# powersupply_grid8_1.net
KiCad netlist of a schematic drawn in Altium Designer
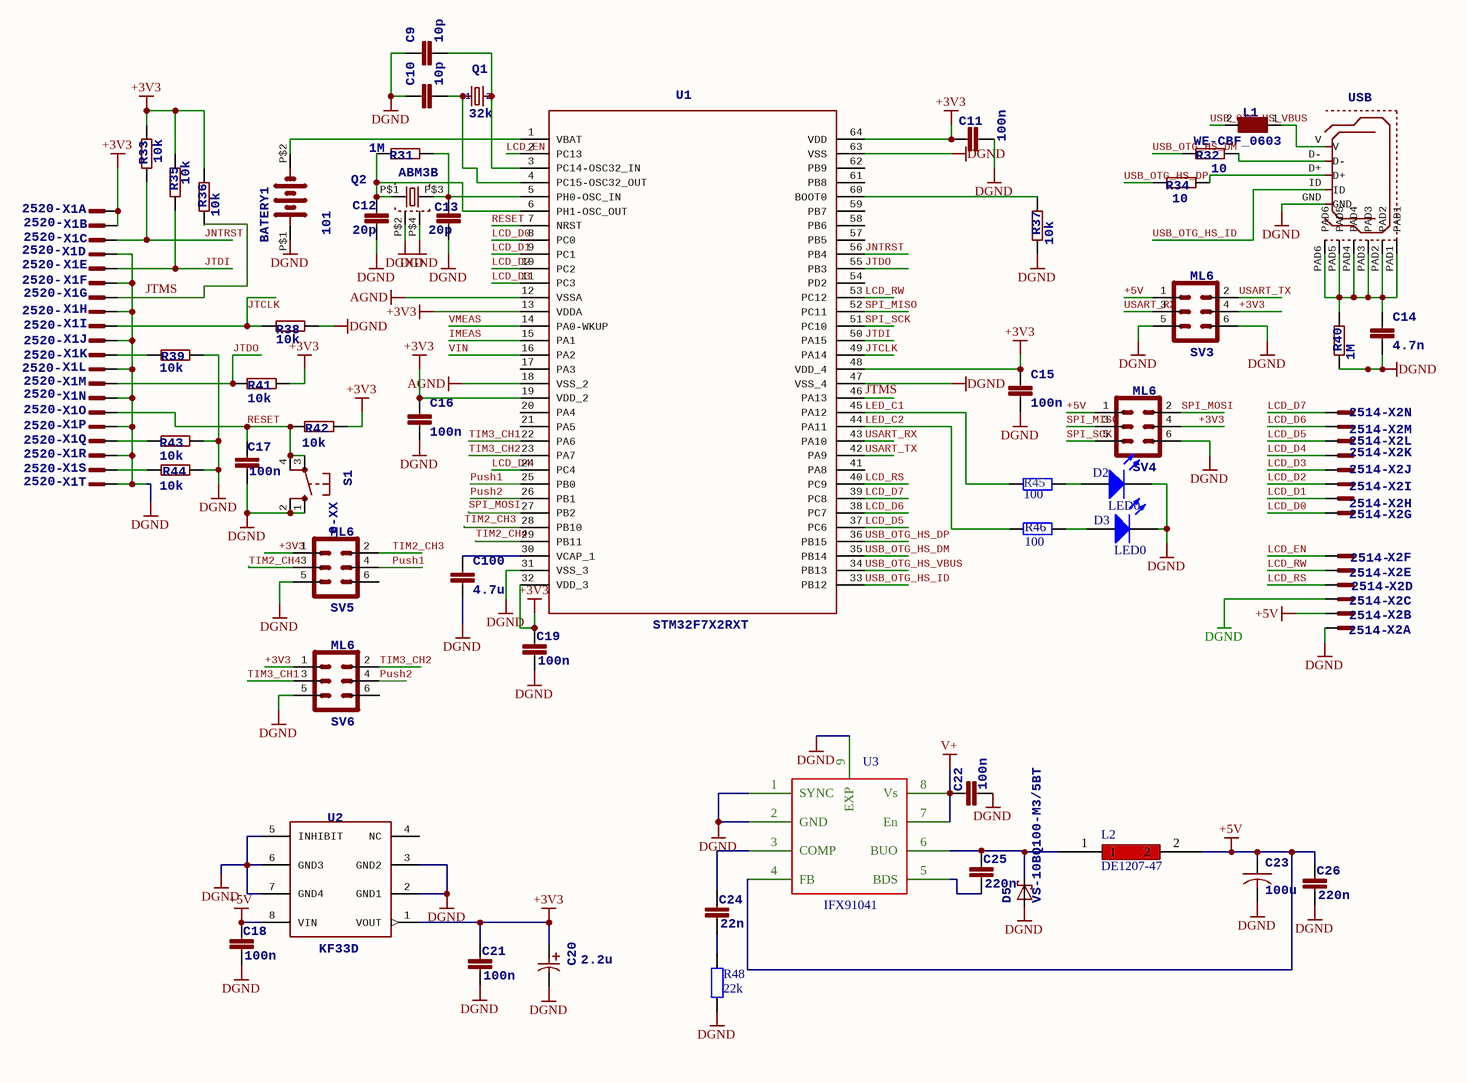
[diagram p0: powersupply_grid8_1.SchDoc]

(export (version "E")
  (design (tool "Eeschema 10.0.6"))
  (components
    (comp (ref "BATERY1") (value "101") (footprint "KEYSTONE101") (libsource (lib "my_battery") (part "101")))
    (comp (ref "C9")
      (value "10p")
      (footprint "C0402")
      (description "<B>CAPACITOR</B>, European symbol")
      (libsource (lib "") (part "C-EUC0402_1"))
    )
    (comp (ref "C10")
      (value "10p")
      (footprint "C0402")
      (description "<B>CAPACITOR</B>, European symbol")
      (libsource (lib "") (part "C-EUC0402_1"))
    )
    (comp (ref "C11")
      (value "100n")
      (footprint "C0402")
      (description "<B>CAPACITOR</B>, European symbol")
      (libsource (lib "") (part "C-EUC0402_1"))
    )
    (comp (ref "C12")
      (value "20p")
      (footprint "C0402")
      (description "<B>CAPACITOR</B>, European symbol")
      (libsource (lib "rcl") (part "C-EUC0402"))
    )
    (comp (ref "C13")
      (value "20p")
      (footprint "C0402")
      (description "<B>CAPACITOR</B>, European symbol")
      (libsource (lib "rcl") (part "C-EUC0402"))
    )
    (comp (ref "C14")
      (value "4.7n")
      (footprint "C0805")
      (description "<B>CAPACITOR</B>, European symbol")
      (libsource (lib "rcl") (part "C-EUC0805"))
    )
    (comp (ref "C15")
      (value "100n")
      (footprint "C0402")
      (description "<B>CAPACITOR</B>, European symbol")
      (libsource (lib "rcl") (part "C-EUC0402"))
    )
    (comp (ref "C16")
      (value "100n")
      (footprint "C0402")
      (description "<B>CAPACITOR</B>, European symbol")
      (libsource (lib "rcl") (part "C-EUC0402"))
    )
    (comp (ref "C17")
      (value "100n")
      (footprint "C0402")
      (description "<B>CAPACITOR</B>, European symbol")
      (libsource (lib "rcl") (part "C-EUC0402"))
    )
    (comp (ref "C18")
      (value "100n")
      (footprint "C0603")
      (description "<B>CAPACITOR</B>, European symbol")
      (libsource (lib "rcl") (part "C-EUC0603"))
    )
    (comp (ref "C19")
      (value "100n")
      (footprint "C0603")
      (description "<B>CAPACITOR</B>, European symbol")
      (libsource (lib "rcl") (part "C-EUC0603"))
    )
    (comp (ref "C20")
      (value "2.2u")
      (footprint "CAPAE430X610N")
      (fields
        (field (name "MPN") "EEE-FT0J101AR")
        (field (name "TOLERANCE") "±20 %")
        (field (name "MPN_1") "EEE-FT1A680AR")
      )
      (libsource (lib "Panasonic-EEEFT_EEEH") (part "EEE--CASE-B"))
    )
    (comp (ref "C21")
      (value "100n")
      (footprint "C0603")
      (description "<B>CAPACITOR</B>, European symbol")
      (libsource (lib "rcl") (part "C-EUC0603"))
    )
    (comp (ref "C22")
      (value "100n")
      (footprint "C0603")
      (description "<B>CAPACITOR</B>, European symbol")
      (libsource (lib "") (part "C-EUC0603_1"))
    )
    (comp (ref "C23") (value "100u") (footprint "C2225K") (libsource (lib "rcl") (part "C-USC2225K")))
    (comp (ref "C24")
      (value "22n")
      (footprint "C0603")
      (description "<B>CAPACITOR</B>, European symbol")
      (libsource (lib "rcl") (part "C-EUC0603"))
    )
    (comp (ref "C25")
      (value "220n")
      (footprint "C0603")
      (description "<B>CAPACITOR</B>, European symbol")
      (libsource (lib "rcl") (part "C-EUC0603"))
    )
    (comp (ref "C26")
      (value "220n")
      (footprint "C0603")
      (description "<B>CAPACITOR</B>, European symbol")
      (libsource (lib "rcl") (part "C-EUC0603"))
    )
    (comp (ref "C100") (value "4.7u") (footprint "C0805") (libsource (lib "rcl") (part "C-EUC0805")))
    (comp (ref "D2")
      (value "LED0")
      (footprint "LED-0")
      (description "Typical INFRARED GaAs LED")
      (fields (field (name "PUBLISHER") "Altium Limited"))
      (libsource (lib "Miscellaneous Devices") (part "LED0"))
    )
    (comp (ref "D3")
      (value "LED0")
      (footprint "LED-0")
      (description "Typical INFRARED GaAs LED")
      (fields (field (name "PUBLISHER") "Altium Limited"))
      (libsource (lib "Miscellaneous Devices") (part "LED0"))
    )
    (comp (ref "D5")
      (value "VS-10BQ100-M3/5BT")
      (footprint "DO214AA")
      (libsource (lib "VS-10BQ100-M3") (part "SCHOTTKY-DIODEAG"))
    )
    (comp (ref "L1")
      (value "WE-CBF_0603")
      (footprint "0603")
      (fields (field (name "MPN") "742792695"))
      (libsource (lib "WE-CBF") (part "WE-CBF_0603"))
    )
    (comp (ref "L2") (value "DE1207-47") (footprint "DE1207") (libsource (lib "de1207") (part "DE 1207")))
    (comp (ref "Q1")
      (value "32k")
      (footprint "TC26V")
      (description "<b>CRYSTAL</b>")
      (fields (field (name "1") "1") (field (name "2") "2"))
      (libsource (lib "crystal") (part "CRYSTALTC26V"))
    )
    (comp (ref "Q2") (value "ABM3B") (footprint "ABM3B") (libsource (lib "crystal_my") (part "ABM3B")))
    (comp (ref "R31")
      (value "1M")
      (footprint "R0402")
      (description "<B>RESISTOR</B>, European symbol")
      (libsource (lib "rcl") (part "R-EU_R0402"))
    )
    (comp (ref "R32")
      (value "10")
      (footprint "R0805")
      (description "<B>RESISTOR</B>, European symbol")
      (libsource (lib "rcl") (part "R-EU_R0805"))
    )
    (comp (ref "R33")
      (value "10k")
      (footprint "R0805")
      (description "<B>RESISTOR</B>, European symbol")
      (libsource (lib "rcl") (part "R-EU_R0805"))
    )
    (comp (ref "R34")
      (value "10")
      (footprint "R0805")
      (description "<B>RESISTOR</B>, European symbol")
      (libsource (lib "rcl") (part "R-EU_R0805"))
    )
    (comp (ref "R35")
      (value "10k")
      (footprint "R0805")
      (description "<B>RESISTOR</B>, European symbol")
      (libsource (lib "rcl") (part "R-EU_R0805"))
    )
    (comp (ref "R36")
      (value "10k")
      (footprint "R0805")
      (description "<B>RESISTOR</B>, European symbol")
      (libsource (lib "rcl") (part "R-EU_R0805"))
    )
    (comp (ref "R37")
      (value "10k")
      (footprint "R0805")
      (description "<B>RESISTOR</B>, European symbol")
      (libsource (lib "rcl") (part "R-EU_R0805"))
    )
    (comp (ref "R38")
      (value "10k")
      (footprint "R0805")
      (description "<B>RESISTOR</B>, European symbol")
      (libsource (lib "rcl") (part "R-EU_R0805"))
    )
    (comp (ref "R39")
      (value "10k")
      (footprint "R0805")
      (description "<B>RESISTOR</B>, European symbol")
      (libsource (lib "rcl") (part "R-EU_R0805"))
    )
    (comp (ref "R40")
      (value "1M")
      (footprint "R0805")
      (description "<B>RESISTOR</B>, European symbol")
      (libsource (lib "rcl") (part "R-EU_R0805"))
    )
    (comp (ref "R41")
      (value "10k")
      (footprint "R0805")
      (description "<B>RESISTOR</B>, European symbol")
      (libsource (lib "rcl") (part "R-EU_R0805"))
    )
    (comp (ref "R42")
      (value "10k")
      (footprint "R0805")
      (description "<B>RESISTOR</B>, European symbol")
      (libsource (lib "rcl") (part "R-EU_R0805"))
    )
    (comp (ref "R43")
      (value "10k")
      (footprint "R0805")
      (description "<B>RESISTOR</B>, European symbol")
      (libsource (lib "rcl") (part "R-EU_R0805"))
    )
    (comp (ref "R44")
      (value "10k")
      (footprint "R0805")
      (description "<B>RESISTOR</B>, European symbol")
      (libsource (lib "rcl") (part "R-EU_R0805"))
    )
    (comp (ref "R45")
      (value "100")
      (footprint "6-0805_L")
      (description "Resistor")
      (fields (field (name "Comment") "Res2") (field (name "PUBLISHER") "Altium Limited"))
      (libsource (lib "") (part "Res2_1"))
    )
    (comp (ref "R46")
      (value "100")
      (footprint "6-0805_L")
      (description "Resistor")
      (fields (field (name "Comment") "Res2") (field (name "PUBLISHER") "Altium Limited"))
      (libsource (lib "") (part "Res2_1"))
    )
    (comp (ref "R48")
      (value "22k")
      (footprint "6-0805_L")
      (description "Resistor")
      (fields (field (name "Comment") "Res2") (field (name "PUBLISHER") "Altium Limited"))
      (libsource (lib "Miscellaneous Devices") (part "Res2"))
    )
    (comp (ref "S1")
      (value "10-XX")
      (footprint "B3F-10XX")
      (description "<b>OMRON SWITCH</b>")
      (fields (field (name "MPN") "B3F-1000"))
      (libsource (lib "switch-omron") (part "10-XX"))
    )
    (comp (ref "SV3")
      (value "ML6")
      (footprint "ML6")
      (description "<b>HARTING</b>")
      (libsource (lib "con-harting-ml") (part "ML6"))
    )
    (comp (ref "SV4")
      (value "ML6")
      (footprint "ML6")
      (description "<b>HARTING</b>")
      (libsource (lib "con-harting-ml") (part "ML6"))
    )
    (comp (ref "SV5")
      (value "ML6")
      (footprint "ML6")
      (description "<b>HARTING</b>")
      (libsource (lib "con-harting-ml") (part "ML6"))
    )
    (comp (ref "SV6")
      (value "ML6")
      (footprint "ML6")
      (description "<b>HARTING</b>")
      (libsource (lib "con-harting-ml") (part "ML6"))
    )
    (comp (ref "U$4")
      (value "USB_MICROB")
      (footprint "USB_MICROB_PACKAGE")
      (description "This is the hirose ZX62-B-5PA(11) MICRO-USB B Type female connection.")
      (fields (field (name "USB") "USB"))
      (libsource (lib "usb_hinrose") (part "USB_MICROB"))
    )
    (comp (ref "U1")
      (value "STM32F7X2RXT")
      (footprint "LQFP64-10X10MM")
      (fields (field (name "MANUFACTURER_PART_NUMBER") "stm32f7x2rxt"))
      (libsource (lib "STM32F732RE") (part "STM32F7X2RXT"))
    )
    (comp (ref "U2") (value "KF33D") (footprint "SO8") (libsource (lib "KF33BD") (part "KF33D")))
    (comp (ref "U3")
      (value "IFX91041")
      (footprint "PG-DSO-8-27")
      (description "1.8A DC/DC Step-Down Voltage Regulator")
      (libsource (lib "IFX91041") (part "IFX91041"))
    )
    (comp (ref "X1")
      (value "2520-")
      (footprint "PAK100/2500-20")
      (description "<b>3M (TM) Pak 100 4-Wall Header</b><p>\nSource: 3M")
      (libsource (lib "con-3m") (part "2520-"))
    )
    (comp (ref "X2")
      (value "2514-")
      (footprint "PAK100/2500-14")
      (description "<b>3M (TM) Pak 100 4-Wall Header</b><p>\nSource: 3M")
      (libsource (lib "con-3m") (part "2514-"))
    )
  )
  (nets
    (net (code "1") (name "+3V3") (class "Default")
      (node (ref "C11") (pin "1") (pinfunction "1_1") (pintype "passive"))
      (node (ref "C15") (pin "1") (pinfunction "1_1") (pintype "passive"))
      (node (ref "C16") (pin "1") (pinfunction "1_1") (pintype "passive"))
      (node (ref "C19") (pin "1") (pinfunction "1_1") (pintype "passive"))
      (node (ref "C20") (pin "1") (pinfunction "1_1") (pintype "passive"))
      (node (ref "C21") (pin "1") (pinfunction "1_1") (pintype "passive"))
      (node (ref "R33") (pin "2") (pinfunction "2_2") (pintype "passive"))
      (node (ref "R35") (pin "2") (pinfunction "2_2") (pintype "passive"))
      (node (ref "R36") (pin "2") (pinfunction "2_2") (pintype "passive"))
      (node (ref "R41") (pin "1") (pinfunction "1_1") (pintype "passive"))
      (node (ref "R42") (pin "1") (pinfunction "1_1") (pintype "passive"))
      (node (ref "SV3") (pin "4") (pinfunction "4_4") (pintype "passive"))
      (node (ref "SV4") (pin "4") (pinfunction "4_4") (pintype "passive"))
      (node (ref "SV5") (pin "1") (pinfunction "1_1") (pintype "passive"))
      (node (ref "SV6") (pin "1") (pinfunction "1_1") (pintype "passive"))
      (node (ref "U1") (pin "13") (pinfunction "VDDA_13") (pintype "power_in"))
      (node (ref "U1") (pin "19") (pinfunction "VDD_2_19") (pintype "power_in"))
      (node (ref "U1") (pin "32") (pinfunction "VDD_3_32") (pintype "power_in"))
      (node (ref "U1") (pin "48") (pinfunction "VDD_4_48") (pintype "power_in"))
      (node (ref "U1") (pin "64") (pinfunction "VDD_64") (pintype "power_in"))
      (node (ref "U2") (pin "1") (pinfunction "VOUT_1") (pintype "output"))
      (node (ref "X1") (pin "1") (pinfunction "KL_1") (pintype "passive"))
      (node (ref "X1") (pin "2") (pinfunction "KL_2") (pintype "passive"))
    )
    (net (code "2") (name "+5V") (class "Default")
      (node (ref "C18") (pin "1") (pinfunction "1_1") (pintype "passive"))
      (node (ref "C23") (pin "1") (pinfunction "1_1") (pintype "passive"))
      (node (ref "C26") (pin "1") (pinfunction "1_1") (pintype "passive"))
      (node (ref "L2") (pin "2") (pinfunction "2_2") (pintype "passive"))
      (node (ref "SV3") (pin "1") (pinfunction "1_1") (pintype "passive"))
      (node (ref "SV4") (pin "1") (pinfunction "1_1") (pintype "passive"))
      (node (ref "U2") (pin "8") (pinfunction "VIN_8") (pintype "passive"))
      (node (ref "U3") (pin "4") (pinfunction "FB_4") (pintype "passive"))
      (node (ref "X2") (pin "2") (pinfunction "KL_2") (pintype "passive"))
    )
    (net (code "3") (name "/IMEAS") (class "Default")
      (node (ref "U1") (pin "15") (pinfunction "PA1_15") (pintype "passive"))
    )
    (net (code "4") (name "/JNTRST") (class "Default")
      (node (ref "R33") (pin "1") (pinfunction "1_1") (pintype "passive"))
      (node (ref "U1") (pin "56") (pinfunction "PB4_56") (pintype "passive"))
      (node (ref "X1") (pin "3") (pinfunction "KL_3") (pintype "passive"))
    )
    (net (code "5") (name "/JTCLK") (class "Default")
      (node (ref "R38") (pin "2") (pinfunction "2_2") (pintype "passive"))
      (node (ref "U1") (pin "49") (pinfunction "PA14_49") (pintype "passive"))
      (node (ref "X1") (pin "9") (pinfunction "KL_9") (pintype "passive"))
    )
    (net (code "6") (name "/JTDI") (class "Default")
      (node (ref "R35") (pin "1") (pinfunction "1_1") (pintype "passive"))
      (node (ref "U1") (pin "50") (pinfunction "PA15_50") (pintype "passive"))
      (node (ref "X1") (pin "5") (pinfunction "KL_5") (pintype "passive"))
    )
    (net (code "7") (name "/JTDO") (class "Default")
      (node (ref "R41") (pin "2") (pinfunction "2_2") (pintype "passive"))
      (node (ref "U1") (pin "55") (pinfunction "PB3_55") (pintype "passive"))
      (node (ref "X1") (pin "13") (pinfunction "KL_13") (pintype "passive"))
    )
    (net (code "8") (name "/JTMS") (class "Default")
      (node (ref "R36") (pin "1") (pinfunction "1_1") (pintype "passive"))
      (node (ref "U1") (pin "46") (pinfunction "PA13_46") (pintype "passive"))
      (node (ref "X1") (pin "7") (pinfunction "KL_7") (pintype "passive"))
    )
    (net (code "9") (name "/LCD_D0") (class "Default")
      (node (ref "U1") (pin "8") (pinfunction "PC0_8") (pintype "passive"))
      (node (ref "X2") (pin "7") (pinfunction "KL_7") (pintype "passive"))
    )
    (net (code "10") (name "/LCD_D1") (class "Default")
      (node (ref "U1") (pin "9") (pinfunction "PC1_9") (pintype "passive"))
      (node (ref "X2") (pin "8") (pinfunction "KL_8") (pintype "passive"))
    )
    (net (code "11") (name "/LCD_D2") (class "Default")
      (node (ref "U1") (pin "10") (pinfunction "PC2_10") (pintype "passive"))
      (node (ref "X2") (pin "9") (pinfunction "KL_9") (pintype "passive"))
    )
    (net (code "12") (name "/LCD_D3") (class "Default")
      (node (ref "U1") (pin "11") (pinfunction "PC3_11") (pintype "passive"))
      (node (ref "X2") (pin "10") (pinfunction "KL_10") (pintype "passive"))
    )
    (net (code "13") (name "/LCD_D4") (class "Default")
      (node (ref "U1") (pin "24") (pinfunction "PC4_24") (pintype "passive"))
      (node (ref "X2") (pin "11") (pinfunction "KL_11") (pintype "passive"))
    )
    (net (code "14") (name "/LCD_D5") (class "Default")
      (node (ref "U1") (pin "37") (pinfunction "PC6_37") (pintype "passive"))
      (node (ref "X2") (pin "12") (pinfunction "KL_12") (pintype "passive"))
    )
    (net (code "15") (name "/LCD_D6") (class "Default")
      (node (ref "U1") (pin "38") (pinfunction "PC7_38") (pintype "passive"))
      (node (ref "X2") (pin "13") (pinfunction "KL_13") (pintype "passive"))
    )
    (net (code "16") (name "/LCD_D7") (class "Default")
      (node (ref "U1") (pin "39") (pinfunction "PC8_39") (pintype "passive"))
      (node (ref "X2") (pin "14") (pinfunction "KL_14") (pintype "passive"))
    )
    (net (code "17") (name "/LCD_EN") (class "Default")
      (node (ref "U1") (pin "2") (pinfunction "PC13_2") (pintype "passive"))
      (node (ref "X2") (pin "6") (pinfunction "KL_6") (pintype "passive"))
    )
    (net (code "18") (name "/LCD_RS") (class "Default")
      (node (ref "U1") (pin "40") (pinfunction "PC9_40") (pintype "passive"))
      (node (ref "X2") (pin "4") (pinfunction "KL_4") (pintype "passive"))
    )
    (net (code "19") (name "/LCD_RW") (class "Default")
      (node (ref "U1") (pin "53") (pinfunction "PC12_53") (pintype "passive"))
      (node (ref "X2") (pin "5") (pinfunction "KL_5") (pintype "passive"))
    )
    (net (code "20") (name "/LED_C1") (class "Default")
      (node (ref "R45") (pin "1") (pinfunction "1_1") (pintype "passive"))
      (node (ref "U1") (pin "45") (pinfunction "PA12_45") (pintype "passive"))
    )
    (net (code "21") (name "/LED_C2") (class "Default")
      (node (ref "R46") (pin "1") (pinfunction "1_1") (pintype "passive"))
      (node (ref "U1") (pin "44") (pinfunction "PA11_44") (pintype "passive"))
    )
    (net (code "22") (name "/Push1") (class "Default")
      (node (ref "SV5") (pin "4") (pinfunction "4_4") (pintype "passive"))
      (node (ref "U1") (pin "25") (pinfunction "PB0_25") (pintype "passive"))
    )
    (net (code "23") (name "/Push2") (class "Default")
      (node (ref "SV6") (pin "4") (pinfunction "4_4") (pintype "passive"))
      (node (ref "U1") (pin "26") (pinfunction "PB1_26") (pintype "passive"))
    )
    (net (code "24") (name "/RESET") (class "Default")
      (node (ref "C17") (pin "1") (pinfunction "1_1") (pintype "passive"))
      (node (ref "R42") (pin "2") (pinfunction "2_2") (pintype "passive"))
      (node (ref "S1") (pin "3") (pinfunction "P_3") (pintype "passive"))
      (node (ref "S1") (pin "4") (pinfunction "P1_4") (pintype "passive"))
      (node (ref "U1") (pin "7") (pinfunction "NRST_7") (pintype "passive"))
      (node (ref "X1") (pin "15") (pinfunction "KL_15") (pintype "passive"))
    )
    (net (code "25") (name "/SPI_MISO") (class "Default")
      (node (ref "SV4") (pin "3") (pinfunction "3_3") (pintype "passive"))
      (node (ref "U1") (pin "52") (pinfunction "PC11_52") (pintype "passive"))
    )
    (net (code "26") (name "/SPI_MOSI") (class "Default")
      (node (ref "SV4") (pin "2") (pinfunction "2_2") (pintype "passive"))
      (node (ref "U1") (pin "27") (pinfunction "PB2_27") (pintype "passive"))
    )
    (net (code "27") (name "/SPI_SCK") (class "Default")
      (node (ref "SV4") (pin "5") (pinfunction "5_5") (pintype "passive"))
      (node (ref "U1") (pin "51") (pinfunction "PC10_51") (pintype "passive"))
    )
    (net (code "28") (name "/TIM2_CH3") (class "Default")
      (node (ref "SV5") (pin "2") (pinfunction "2_2") (pintype "passive"))
      (node (ref "U1") (pin "28") (pinfunction "PB10_28") (pintype "passive"))
    )
    (net (code "29") (name "/TIM2_CH4") (class "Default")
      (node (ref "SV5") (pin "3") (pinfunction "3_3") (pintype "passive"))
      (node (ref "U1") (pin "29") (pinfunction "PB11_29") (pintype "passive"))
    )
    (net (code "30") (name "/TIM3_CH1") (class "Default")
      (node (ref "SV6") (pin "3") (pinfunction "3_3") (pintype "passive"))
      (node (ref "U1") (pin "22") (pinfunction "PA6_22") (pintype "passive"))
    )
    (net (code "31") (name "/TIM3_CH2") (class "Default")
      (node (ref "SV6") (pin "2") (pinfunction "2_2") (pintype "passive"))
      (node (ref "U1") (pin "23") (pinfunction "PA7_23") (pintype "passive"))
    )
    (net (code "32") (name "/USART_RX") (class "Default")
      (node (ref "SV3") (pin "3") (pinfunction "3_3") (pintype "passive"))
      (node (ref "U1") (pin "43") (pinfunction "PA10_43") (pintype "passive"))
    )
    (net (code "33") (name "/USART_TX") (class "Default")
      (node (ref "SV3") (pin "2") (pinfunction "2_2") (pintype "passive"))
      (node (ref "U1") (pin "42") (pinfunction "PA9_42") (pintype "passive"))
    )
    (net (code "34") (name "/USB_OTG_HS_DM") (class "Default")
      (node (ref "R32") (pin "2") (pinfunction "2_2") (pintype "passive"))
      (node (ref "U1") (pin "35") (pinfunction "PB14_35") (pintype "passive"))
    )
    (net (code "35") (name "/USB_OTG_HS_DP") (class "Default")
      (node (ref "R34") (pin "2") (pinfunction "2_2") (pintype "passive"))
      (node (ref "U1") (pin "36") (pinfunction "PB15_36") (pintype "passive"))
    )
    (net (code "36") (name "/USB_OTG_HS_ID") (class "Default")
      (node (ref "U$4") (pin "ID") (pinfunction "ID_ID") (pintype "passive"))
      (node (ref "U1") (pin "33") (pinfunction "PB12_33") (pintype "passive"))
    )
    (net (code "37") (name "/USB_OTG_HS_VBUS") (class "Default")
      (node (ref "L1") (pin "2") (pinfunction "2_2") (pintype "passive"))
      (node (ref "U1") (pin "34") (pinfunction "PB13_34") (pintype "passive"))
    )
    (net (code "38") (name "/VIN") (class "Default")
      (node (ref "U1") (pin "16") (pinfunction "PA2_16") (pintype "passive"))
    )
    (net (code "39") (name "/VMEAS") (class "Default")
      (node (ref "U1") (pin "14") (pinfunction "PA0-WKUP_14") (pintype "passive"))
    )
    (net (code "40") (name "AGND") (class "Default")
      (node (ref "U1") (pin "12") (pinfunction "VSSA_12") (pintype "power_in"))
      (node (ref "U1") (pin "18") (pinfunction "VSS_2_18") (pintype "power_in"))
    )
    (net (code "41") (name "DGND") (class "Default")
      (node (ref "BATERY1") (pin "P$1") (pinfunction "+_P$1") (pintype "passive"))
      (node (ref "C10") (pin "1") (pinfunction "1_1") (pintype "passive"))
      (node (ref "C100") (pin "2") (pinfunction "2_2") (pintype "passive"))
      (node (ref "C11") (pin "2") (pinfunction "2_2") (pintype "passive"))
      (node (ref "C12") (pin "2") (pinfunction "2_2") (pintype "passive"))
      (node (ref "C13") (pin "2") (pinfunction "2_2") (pintype "passive"))
      (node (ref "C14") (pin "2") (pinfunction "2_2") (pintype "passive"))
      (node (ref "C15") (pin "2") (pinfunction "2_2") (pintype "passive"))
      (node (ref "C16") (pin "2") (pinfunction "2_2") (pintype "passive"))
      (node (ref "C17") (pin "2") (pinfunction "2_2") (pintype "passive"))
      (node (ref "C18") (pin "2") (pinfunction "2_2") (pintype "passive"))
      (node (ref "C19") (pin "2") (pinfunction "2_2") (pintype "passive"))
      (node (ref "C20") (pin "2") (pinfunction "2_2") (pintype "passive"))
      (node (ref "C21") (pin "2") (pinfunction "2_2") (pintype "passive"))
      (node (ref "C22") (pin "2") (pinfunction "2_2") (pintype "passive"))
      (node (ref "C23") (pin "2") (pinfunction "2_2") (pintype "passive"))
      (node (ref "C26") (pin "2") (pinfunction "2_2") (pintype "passive"))
      (node (ref "C9") (pin "1") (pinfunction "1_1") (pintype "passive"))
      (node (ref "D2") (pin "2") (pinfunction "K_2") (pintype "passive"))
      (node (ref "D3") (pin "2") (pinfunction "K_2") (pintype "passive"))
      (node (ref "D5") (pin "A") (pinfunction "A_A") (pintype "passive"))
      (node (ref "Q2") (pin "P$2") (pinfunction "2_P$2") (pintype "passive"))
      (node (ref "Q2") (pin "P$4") (pinfunction "4_P$4") (pintype "passive"))
      (node (ref "R37") (pin "1") (pinfunction "1_1") (pintype "passive"))
      (node (ref "R38") (pin "1") (pinfunction "1_1") (pintype "passive"))
      (node (ref "R39") (pin "1") (pinfunction "1_1") (pintype "passive"))
      (node (ref "R40") (pin "1") (pinfunction "1_1") (pintype "passive"))
      (node (ref "R43") (pin "1") (pinfunction "1_1") (pintype "passive"))
      (node (ref "R44") (pin "1") (pinfunction "1_1") (pintype "passive"))
      (node (ref "R48") (pin "1") (pinfunction "1_1") (pintype "passive"))
      (node (ref "S1") (pin "1") (pinfunction "S_1") (pintype "passive"))
      (node (ref "S1") (pin "2") (pinfunction "S1_2") (pintype "passive"))
      (node (ref "SV3") (pin "5") (pinfunction "5_5") (pintype "passive"))
      (node (ref "SV3") (pin "6") (pinfunction "6_6") (pintype "passive"))
      (node (ref "SV4") (pin "6") (pinfunction "6_6") (pintype "passive"))
      (node (ref "SV5") (pin "5") (pinfunction "5_5") (pintype "passive"))
      (node (ref "SV6") (pin "5") (pinfunction "5_5") (pintype "passive"))
      (node (ref "U$4") (pin "GND") (pinfunction "GND_GND") (pintype "passive"))
      (node (ref "U1") (pin "31") (pinfunction "VSS_3_31") (pintype "power_in"))
      (node (ref "U1") (pin "47") (pinfunction "VSS_4_47") (pintype "power_in"))
      (node (ref "U1") (pin "63") (pinfunction "VSS_63") (pintype "power_in"))
      (node (ref "U2") (pin "2") (pinfunction "GND1_2") (pintype "power_in"))
      (node (ref "U2") (pin "3") (pinfunction "GND2_3") (pintype "power_in"))
      (node (ref "U2") (pin "5") (pinfunction "INHIBIT_5") (pintype "passive"))
      (node (ref "U2") (pin "6") (pinfunction "GND3_6") (pintype "power_in"))
      (node (ref "U2") (pin "7") (pinfunction "GND4_7") (pintype "power_in"))
      (node (ref "U3") (pin "1") (pinfunction "SYNC_1") (pintype "passive"))
      (node (ref "U3") (pin "2") (pinfunction "GND_2") (pintype "passive"))
      (node (ref "U3") (pin "9") (pinfunction "EXP_9") (pintype "passive"))
      (node (ref "X1") (pin "10") (pinfunction "KL_10") (pintype "passive"))
      (node (ref "X1") (pin "12") (pinfunction "KL_12") (pintype "passive"))
      (node (ref "X1") (pin "14") (pinfunction "KL_14") (pintype "passive"))
      (node (ref "X1") (pin "16") (pinfunction "KL_16") (pintype "passive"))
      (node (ref "X1") (pin "18") (pinfunction "KL_18") (pintype "passive"))
      (node (ref "X1") (pin "20") (pinfunction "KL_20") (pintype "passive"))
      (node (ref "X1") (pin "4") (pinfunction "KL_4") (pintype "passive"))
      (node (ref "X1") (pin "6") (pinfunction "KL_6") (pintype "passive"))
      (node (ref "X1") (pin "8") (pinfunction "KL_8") (pintype "passive"))
      (node (ref "X2") (pin "1") (pinfunction "KL_1") (pintype "passive"))
      (node (ref "X2") (pin "3") (pinfunction "KL_3") (pintype "passive"))
    )
    (net (code "42") (name "Net-(BATERY1--)") (class "Default")
      (node (ref "BATERY1") (pin "P$2") (pinfunction "-_P$2") (pintype "passive"))
      (node (ref "U1") (pin "1") (pinfunction "VBAT_1") (pintype "power_in"))
    )
    (net (code "43") (name "Net-(C14-Pad1)") (class "Default")
      (node (ref "C14") (pin "1") (pinfunction "1_1") (pintype "passive"))
      (node (ref "R40") (pin "2") (pinfunction "2_2") (pintype "passive"))
      (node (ref "U$4") (pin "PAD1") (pinfunction "PAD1_PAD1") (pintype "passive"))
      (node (ref "U$4") (pin "PAD2") (pinfunction "PAD2_PAD2") (pintype "passive"))
      (node (ref "U$4") (pin "PAD3") (pinfunction "PAD3_PAD3") (pintype "passive"))
      (node (ref "U$4") (pin "PAD4") (pinfunction "PAD4_PAD4") (pintype "passive"))
      (node (ref "U$4") (pin "PAD5") (pinfunction "PAD5_PAD5") (pintype "passive"))
      (node (ref "U$4") (pin "PAD6") (pinfunction "PAD6_PAD6") (pintype "passive"))
    )
    (net (code "44") (name "Net-(C24-Pad2)") (class "Default")
      (node (ref "C24") (pin "2") (pinfunction "2_2") (pintype "passive"))
      (node (ref "R48") (pin "2") (pinfunction "2_2") (pintype "passive"))
    )
    (net (code "45") (name "Net-(D2-A)") (class "Default")
      (node (ref "D2") (pin "1") (pinfunction "A_1") (pintype "passive"))
      (node (ref "R45") (pin "2") (pinfunction "2_2") (pintype "passive"))
    )
    (net (code "46") (name "Net-(D3-A)") (class "Default")
      (node (ref "D3") (pin "1") (pinfunction "A_1") (pintype "passive"))
      (node (ref "R46") (pin "2") (pinfunction "2_2") (pintype "passive"))
    )
    (net (code "47") (name "Net-(L1-Pad1)") (class "Default")
      (node (ref "L1") (pin "1") (pinfunction "1_1") (pintype "passive"))
      (node (ref "U$4") (pin "V") (pinfunction "V_V") (pintype "passive"))
    )
    (net (code "48") (name "Net-(Q2-1)") (class "Default")
      (node (ref "C12") (pin "1") (pinfunction "1_1") (pintype "passive"))
      (node (ref "Q2") (pin "P$1") (pinfunction "1_P$1") (pintype "passive"))
      (node (ref "R31") (pin "2") (pinfunction "2_2") (pintype "passive"))
      (node (ref "U1") (pin "6") (pinfunction "PH1-OSC_OUT_6") (pintype "passive"))
    )
    (net (code "49") (name "Net-(Q2-3)") (class "Default")
      (node (ref "C13") (pin "1") (pinfunction "1_1") (pintype "passive"))
      (node (ref "Q2") (pin "P$3") (pinfunction "3_P$3") (pintype "passive"))
      (node (ref "R31") (pin "1") (pinfunction "1_1") (pintype "passive"))
      (node (ref "U1") (pin "5") (pinfunction "PH0-OSC_IN_5") (pintype "passive"))
    )
    (net (code "50") (name "Net-(R32-Pad1)") (class "Default")
      (node (ref "R32") (pin "1") (pinfunction "1_1") (pintype "passive"))
      (node (ref "U$4") (pin "D-") (pinfunction "D-_D-") (pintype "passive"))
    )
    (net (code "51") (name "Net-(R34-Pad1)") (class "Default")
      (node (ref "R34") (pin "1") (pinfunction "1_1") (pintype "passive"))
      (node (ref "U$4") (pin "D+") (pinfunction "D+_D+") (pintype "passive"))
    )
    (net (code "52") (name "Net-(U1-BOOT0)") (class "Default")
      (node (ref "R37") (pin "2") (pinfunction "2_2") (pintype "passive"))
      (node (ref "U1") (pin "60") (pinfunction "BOOT0_60") (pintype "passive"))
    )
    (net (code "53") (name "Net-(U1-PC14-OSC32_IN)") (class "Default")
      (node (ref "C9") (pin "2") (pinfunction "2_2") (pintype "passive"))
      (node (ref "Q1") (pin "2") (pinfunction "2_2") (pintype "passive"))
      (node (ref "U1") (pin "3") (pinfunction "PC14-OSC32_IN_3") (pintype "passive"))
    )
    (net (code "54") (name "Net-(U1-PC15-OSC32_OUT)") (class "Default")
      (node (ref "C10") (pin "2") (pinfunction "2_2") (pintype "passive"))
      (node (ref "Q1") (pin "1") (pinfunction "1_1") (pintype "passive"))
      (node (ref "U1") (pin "4") (pinfunction "PC15-OSC32_OUT_4") (pintype "passive"))
    )
    (net (code "55") (name "Net-(U1-VCAP_1)") (class "Default")
      (node (ref "C100") (pin "1") (pinfunction "1_1") (pintype "passive"))
      (node (ref "U1") (pin "30") (pinfunction "VCAP_1_30") (pintype "power_in"))
    )
    (net (code "56") (name "Net-(U3-BDS)") (class "Default")
      (node (ref "C25") (pin "2") (pinfunction "2_2") (pintype "passive"))
      (node (ref "U3") (pin "5") (pinfunction "BDS_5") (pintype "passive"))
    )
    (net (code "57") (name "Net-(U3-BUO)") (class "Default")
      (node (ref "C25") (pin "1") (pinfunction "1_1") (pintype "passive"))
      (node (ref "D5") (pin "C") (pinfunction "C_C") (pintype "passive"))
      (node (ref "L2") (pin "1") (pinfunction "1_1") (pintype "passive"))
      (node (ref "U3") (pin "6") (pinfunction "BUO_6") (pintype "passive"))
    )
    (net (code "58") (name "Net-(U3-COMP)") (class "Default")
      (node (ref "C24") (pin "1") (pinfunction "1_1") (pintype "passive"))
      (node (ref "U3") (pin "3") (pinfunction "COMP_3") (pintype "passive"))
    )
    (net (code "59") (name "Net-(X1K-KL)") (class "Default")
      (node (ref "R39") (pin "2") (pinfunction "2_2") (pintype "passive"))
      (node (ref "X1") (pin "11") (pinfunction "KL_11") (pintype "passive"))
    )
    (net (code "60") (name "Net-(X1Q-KL)") (class "Default")
      (node (ref "R43") (pin "2") (pinfunction "2_2") (pintype "passive"))
      (node (ref "X1") (pin "17") (pinfunction "KL_17") (pintype "passive"))
    )
    (net (code "61") (name "Net-(X1S-KL)") (class "Default")
      (node (ref "R44") (pin "2") (pinfunction "2_2") (pintype "passive"))
      (node (ref "X1") (pin "19") (pinfunction "KL_19") (pintype "passive"))
    )
    (net (code "62") (name "V+") (class "Default")
      (node (ref "C22") (pin "1") (pinfunction "1_1") (pintype "passive"))
      (node (ref "U3") (pin "7") (pinfunction "En_7") (pintype "passive"))
      (node (ref "U3") (pin "8") (pinfunction "Vs_8") (pintype "passive"))
    )
    (net (code "63") (name "unconnected-(SV5-Pad6)") (class "Default")
      (node (ref "SV5") (pin "6") (pinfunction "6_6") (pintype "passive"))
    )
    (net (code "64") (name "unconnected-(SV6-Pad6)") (class "Default")
      (node (ref "SV6") (pin "6") (pinfunction "6_6") (pintype "passive"))
    )
    (net (code "65") (name "unconnected-(U1-PA3-Pad17)") (class "Default")
      (node (ref "U1") (pin "17") (pinfunction "PA3_17") (pintype "passive"))
    )
    (net (code "66") (name "unconnected-(U1-PA4-Pad20)") (class "Default")
      (node (ref "U1") (pin "20") (pinfunction "PA4_20") (pintype "passive"))
    )
    (net (code "67") (name "unconnected-(U1-PA5-Pad21)") (class "Default")
      (node (ref "U1") (pin "21") (pinfunction "PA5_21") (pintype "passive"))
    )
    (net (code "68") (name "unconnected-(U1-PA8-Pad41)") (class "Default")
      (node (ref "U1") (pin "41") (pinfunction "PA8_41") (pintype "passive"))
    )
    (net (code "69") (name "unconnected-(U1-PB5-Pad57)") (class "Default")
      (node (ref "U1") (pin "57") (pinfunction "PB5_57") (pintype "passive"))
    )
    (net (code "70") (name "unconnected-(U1-PB6-Pad58)") (class "Default")
      (node (ref "U1") (pin "58") (pinfunction "PB6_58") (pintype "passive"))
    )
    (net (code "71") (name "unconnected-(U1-PB7-Pad59)") (class "Default")
      (node (ref "U1") (pin "59") (pinfunction "PB7_59") (pintype "passive"))
    )
    (net (code "72") (name "unconnected-(U1-PB8-Pad61)") (class "Default")
      (node (ref "U1") (pin "61") (pinfunction "PB8_61") (pintype "passive"))
    )
    (net (code "73") (name "unconnected-(U1-PB9-Pad62)") (class "Default")
      (node (ref "U1") (pin "62") (pinfunction "PB9_62") (pintype "passive"))
    )
    (net (code "74") (name "unconnected-(U1-PD2-Pad54)") (class "Default")
      (node (ref "U1") (pin "54") (pinfunction "PD2_54") (pintype "passive"))
    )
    (net (code "75") (name "unconnected-(U2-NC-Pad4)") (class "Default")
      (node (ref "U2") (pin "4") (pinfunction "NC_4") (pintype "passive"))
    )
  )
)
